# schematic.net
KiCad netlist of a schematic drawn in EAGLE
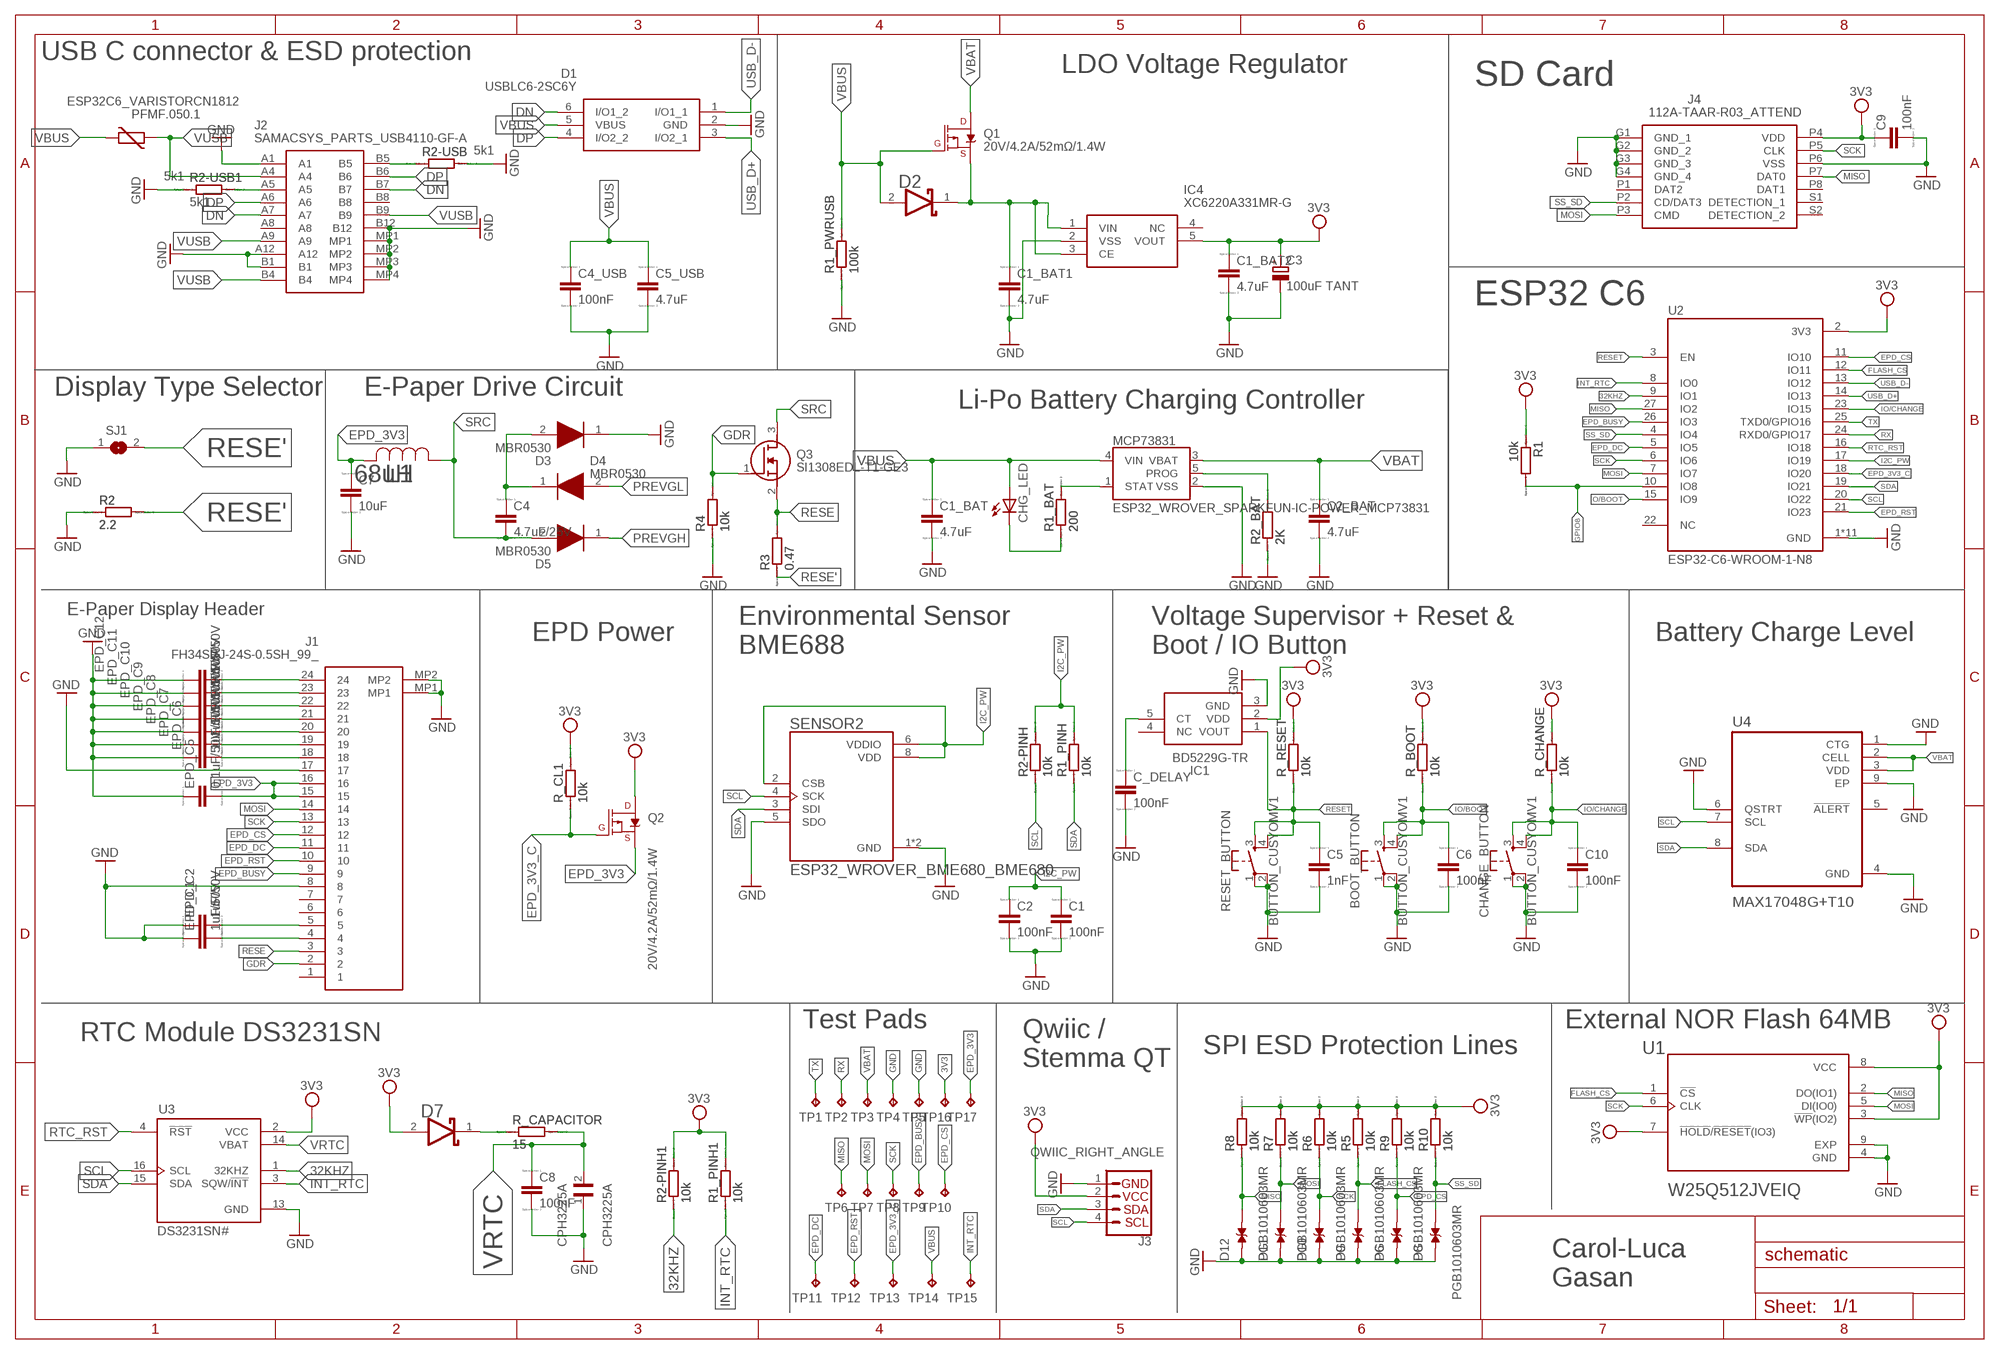
[diagram p0: schematic, sheet 1]

(export (version "E")
  (design (tool "Eeschema 10.0.6"))
  (components
    (comp (ref "BOOT_BUTTON")
      (value "BUTTON_CUSYOMV1")
      (footprint "eagle-import:MYBUTTON")
      (libsource (lib "eagle-import") (part "BUTTON_CUSYOMV1"))
    )
    (comp (ref "C1")
      (value "100nF")
      (footprint "eagle-import:ESP32_WROVER_EAGLE-LTSPICE_C0402")
      (libsource (lib "eagle-import") (part "ESP32_WROVER_EAGLE-LTSPICE_CC0402"))
    )
    (comp (ref "C1_BAT")
      (value "4.7uF")
      (footprint "eagle-import:ESP32_WROVER_EAGLE-LTSPICE_C0402")
      (libsource (lib "eagle-import") (part "ESP32_WROVER_EAGLE-LTSPICE_CC0402"))
    )
    (comp (ref "C1_BAT1")
      (value "4.7uF")
      (footprint "eagle-import:ESP32_WROVER_EAGLE-LTSPICE_C0402")
      (libsource (lib "eagle-import") (part "ESP32_WROVER_EAGLE-LTSPICE_CC0402"))
    )
    (comp (ref "C1_BAT2")
      (value "4.7uF")
      (footprint "eagle-import:ESP32_WROVER_EAGLE-LTSPICE_C0402")
      (libsource (lib "eagle-import") (part "ESP32_WROVER_EAGLE-LTSPICE_CC0402"))
    )
    (comp (ref "C2")
      (value "100nF")
      (footprint "eagle-import:ESP32_WROVER_EAGLE-LTSPICE_C0402")
      (libsource (lib "eagle-import") (part "ESP32_WROVER_EAGLE-LTSPICE_CC0402"))
    )
    (comp (ref "C2_BAT")
      (value "4.7uF")
      (footprint "eagle-import:ESP32_WROVER_EAGLE-LTSPICE_C0402")
      (libsource (lib "eagle-import") (part "ESP32_WROVER_EAGLE-LTSPICE_CC0402"))
    )
    (comp (ref "C3")
      (value "100uF TANT")
      (footprint "eagle-import:RCL_CT3528")
      (libsource (lib "eagle-import") (part "RCL_CPOL-EUCT3528"))
    )
    (comp (ref "C4")
      (value "4.7uF/25V")
      (footprint "eagle-import:ESP32_WROVER_EAGLE-LTSPICE_C0402")
      (libsource (lib "eagle-import") (part "ESP32_WROVER_EAGLE-LTSPICE_CC0402"))
    )
    (comp (ref "C4_USB")
      (value "100nF")
      (footprint "eagle-import:ESP32_WROVER_EAGLE-LTSPICE_C0402")
      (libsource (lib "eagle-import") (part "ESP32_WROVER_EAGLE-LTSPICE_CC0402"))
    )
    (comp (ref "C5")
      (value "1nF")
      (footprint "eagle-import:ESP32_WROVER_EAGLE-LTSPICE_C0402")
      (libsource (lib "eagle-import") (part "ESP32_WROVER_EAGLE-LTSPICE_CC0402"))
    )
    (comp (ref "C5_USB")
      (value "4.7uF")
      (footprint "eagle-import:ESP32_WROVER_EAGLE-LTSPICE_C0402")
      (libsource (lib "eagle-import") (part "ESP32_WROVER_EAGLE-LTSPICE_CC0402"))
    )
    (comp (ref "C6")
      (value "100nF")
      (footprint "eagle-import:ESP32_WROVER_EAGLE-LTSPICE_C0402")
      (libsource (lib "eagle-import") (part "ESP32_WROVER_EAGLE-LTSPICE_CC0402"))
    )
    (comp (ref "C7")
      (value "10uF")
      (footprint "eagle-import:ESP32_WROVER_EAGLE-LTSPICE_C0402")
      (libsource (lib "eagle-import") (part "ESP32_WROVER_EAGLE-LTSPICE_CC0402"))
    )
    (comp (ref "C8")
      (value "100nF")
      (footprint "eagle-import:ESP32_WROVER_EAGLE-LTSPICE_C0402")
      (libsource (lib "eagle-import") (part "ESP32_WROVER_EAGLE-LTSPICE_CC0402"))
    )
    (comp (ref "C9")
      (value "100nF")
      (footprint "eagle-import:ESP32_WROVER_EAGLE-LTSPICE_C0402")
      (libsource (lib "eagle-import") (part "ESP32_WROVER_EAGLE-LTSPICE_CC0402"))
    )
    (comp (ref "C10")
      (value "100nF")
      (footprint "eagle-import:ESP32_WROVER_EAGLE-LTSPICE_C0402")
      (libsource (lib "eagle-import") (part "ESP32_WROVER_EAGLE-LTSPICE_CC0402"))
    )
    (comp (ref "CHANGE_BUTTON")
      (value "BUTTON_CUSYOMV1")
      (footprint "eagle-import:MYBUTTON")
      (libsource (lib "eagle-import") (part "BUTTON_CUSYOMV1"))
    )
    (comp (ref "CHG_LED")
      (value "ADAFRUIT_LEDCHIP-LED0603")
      (footprint "eagle-import:ADAFRUIT_CHIP-LED0603")
      (libsource (lib "eagle-import") (part "ADAFRUIT_LEDCHIP-LED0603"))
    )
    (comp (ref "CPH3225A")
      (value "CPH3225A")
      (footprint "eagle-import:CAPCP3225X100N")
      (fields (field (name "MF") "Seiko Instruments"))
      (libsource (lib "eagle-import") (part "CPH3225A"))
    )
    (comp (ref "C_DELAY")
      (value "100nF")
      (footprint "eagle-import:ESP32_WROVER_EAGLE-LTSPICE_C0402")
      (libsource (lib "eagle-import") (part "ESP32_WROVER_EAGLE-LTSPICE_CC0402"))
    )
    (comp (ref "D1")
      (value "USBLC6-2SC6Y")
      (footprint "eagle-import:SOT95P280X145-6N")
      (fields (field (name "MF") "STMicroelectronics"))
      (libsource (lib "eagle-import") (part "USBLC6-2SC6Y"))
    )
    (comp (ref "D2")
      (value "ESP32_WROVER_AVX---SD0805S020S1R0_AVX_SD0805S020S1R0_0_0AVX_SD0805S020S1R0_0_0")
      (footprint "eagle-import:ESP32_WROVER_AVX---SD0805S020S1R0_AVX_SD0805S020S1R0_0")
      (fields
        (field (name "DIGIKEY_PART_NUMBER") "478-7800-1-ND")
        (field (name "MF") "AVX")
        (field (name "MOUSER_PART_NUMBER") "581-SD0805S020S1R0")
      )
      (libsource (lib "eagle-import") (part "ESP32_WROVER_AVX---SD0805S020S1R0_AVX_SD0805S020S1R0_0_0AVX_SD0805S020S1R0_0_0"))
    )
    (comp (ref "D3")
      (value "MBR0530")
      (footprint "eagle-import:SOD3716X135N")
      (fields (field (name "MF") "ON Semiconductor"))
      (libsource (lib "eagle-import") (part "MBR0530"))
    )
    (comp (ref "D4")
      (value "MBR0530")
      (footprint "eagle-import:SOD3716X135N")
      (fields (field (name "MF") "ON Semiconductor"))
      (libsource (lib "eagle-import") (part "MBR0530"))
    )
    (comp (ref "D5")
      (value "MBR0530")
      (footprint "eagle-import:SOD3716X135N")
      (fields (field (name "MF") "ON Semiconductor"))
      (libsource (lib "eagle-import") (part "MBR0530"))
    )
    (comp (ref "D6")
      (value "PGB1010603MR")
      (footprint "eagle-import:DIOC1608X36N")
      (fields (field (name "MF") "Littelfuse Inc."))
      (libsource (lib "eagle-import") (part "PGB1010603MR"))
    )
    (comp (ref "D7")
      (value "ESP32_WROVER_AVX---SD0805S020S1R0_AVX_SD0805S020S1R0_0_0AVX_SD0805S020S1R0_0_0")
      (footprint "eagle-import:ESP32_WROVER_AVX---SD0805S020S1R0_AVX_SD0805S020S1R0_0")
      (fields
        (field (name "DIGIKEY_PART_NUMBER") "478-7800-1-ND")
        (field (name "MF") "AVX")
        (field (name "MOUSER_PART_NUMBER") "581-SD0805S020S1R0")
      )
      (libsource (lib "eagle-import") (part "ESP32_WROVER_AVX---SD0805S020S1R0_AVX_SD0805S020S1R0_0_0AVX_SD0805S020S1R0_0_0"))
    )
    (comp (ref "D8")
      (value "PGB1010603MR")
      (footprint "eagle-import:DIOC1608X36N")
      (fields (field (name "MF") "Littelfuse Inc."))
      (libsource (lib "eagle-import") (part "PGB1010603MR"))
    )
    (comp (ref "D9")
      (value "PGB1010603MR")
      (footprint "eagle-import:DIOC1608X36N")
      (fields (field (name "MF") "Littelfuse Inc."))
      (libsource (lib "eagle-import") (part "PGB1010603MR"))
    )
    (comp (ref "D10")
      (value "PGB1010603MR")
      (footprint "eagle-import:DIOC1608X36N")
      (fields (field (name "MF") "Littelfuse Inc."))
      (libsource (lib "eagle-import") (part "PGB1010603MR"))
    )
    (comp (ref "D11")
      (value "PGB1010603MR")
      (footprint "eagle-import:DIOC1608X36N")
      (fields (field (name "MF") "Littelfuse Inc."))
      (libsource (lib "eagle-import") (part "PGB1010603MR"))
    )
    (comp (ref "D12")
      (value "PGB1010603MR")
      (footprint "eagle-import:DIOC1608X36N")
      (fields (field (name "MF") "Littelfuse Inc."))
      (libsource (lib "eagle-import") (part "PGB1010603MR"))
    )
    (comp (ref "EPD_C1")
      (value "1uF/50V")
      (footprint "eagle-import:ESP32_WROVER_EAGLE-LTSPICE_C0402")
      (libsource (lib "eagle-import") (part "ESP32_WROVER_EAGLE-LTSPICE_CC0402"))
    )
    (comp (ref "EPD_C2")
      (value "1uF/50V")
      (footprint "eagle-import:ESP32_WROVER_EAGLE-LTSPICE_C0402")
      (libsource (lib "eagle-import") (part "ESP32_WROVER_EAGLE-LTSPICE_CC0402"))
    )
    (comp (ref "EPD_C5")
      (value "0.1uF/50V")
      (footprint "eagle-import:ESP32_WROVER_EAGLE-LTSPICE_C0402")
      (libsource (lib "eagle-import") (part "ESP32_WROVER_EAGLE-LTSPICE_CC0402"))
    )
    (comp (ref "EPD_C6")
      (value "1uF/50V")
      (footprint "eagle-import:ESP32_WROVER_EAGLE-LTSPICE_C0402")
      (libsource (lib "eagle-import") (part "ESP32_WROVER_EAGLE-LTSPICE_CC0402"))
    )
    (comp (ref "EPD_C7")
      (value "1uF/50V")
      (footprint "eagle-import:ESP32_WROVER_EAGLE-LTSPICE_C0402")
      (libsource (lib "eagle-import") (part "ESP32_WROVER_EAGLE-LTSPICE_CC0402"))
    )
    (comp (ref "EPD_C8")
      (value "1uF/50V")
      (footprint "eagle-import:ESP32_WROVER_EAGLE-LTSPICE_C0402")
      (libsource (lib "eagle-import") (part "ESP32_WROVER_EAGLE-LTSPICE_CC0402"))
    )
    (comp (ref "EPD_C9")
      (value "1uF/50V")
      (footprint "eagle-import:ESP32_WROVER_EAGLE-LTSPICE_C0402")
      (libsource (lib "eagle-import") (part "ESP32_WROVER_EAGLE-LTSPICE_CC0402"))
    )
    (comp (ref "EPD_C10")
      (value "1uF/50V")
      (footprint "eagle-import:ESP32_WROVER_EAGLE-LTSPICE_C0402")
      (libsource (lib "eagle-import") (part "ESP32_WROVER_EAGLE-LTSPICE_CC0402"))
    )
    (comp (ref "EPD_C11")
      (value "1uF/50V")
      (footprint "eagle-import:ESP32_WROVER_EAGLE-LTSPICE_C0402")
      (libsource (lib "eagle-import") (part "ESP32_WROVER_EAGLE-LTSPICE_CC0402"))
    )
    (comp (ref "EPD_C12")
      (value "1uF/50V")
      (footprint "eagle-import:ESP32_WROVER_EAGLE-LTSPICE_C0402")
      (libsource (lib "eagle-import") (part "ESP32_WROVER_EAGLE-LTSPICE_CC0402"))
    )
    (comp (ref "IC1")
      (value "BD5229G-TR")
      (footprint "eagle-import:SOT95P280X125-5N")
      (fields (field (name "MOUSER_PART_NUMBER") "755-BD5229G-TR"))
      (libsource (lib "eagle-import") (part "BD5229G-TR"))
    )
    (comp (ref "IC4")
      (value "XC6220A331MR-G")
      (footprint "eagle-import:SOT95P280X120-5N")
      (fields (field (name "MOUSER_PART_NUMBER") "865-XC6220A331MR-G"))
      (libsource (lib "eagle-import") (part "XC6220A331MR-G"))
    )
    (comp (ref "J1")
      (value "FH34SRJ-24S-0.5SH_99_")
      (footprint "eagle-import:FH34SRJ24S05SH99")
      (fields
        (field (name "MANUFACTURER_PART_NUMBER") "FH34SRJ-24S-0.5SH(99)")
        (field (name "MOUSER_PART_NUMBER") "798-FH34SRJ24S05SH99")
      )
      (libsource (lib "eagle-import") (part "FH34SRJ-24S-0.5SH_99_"))
    )
    (comp (ref "J2")
      (value "SAMACSYS_PARTS_USB4110-GF-A")
      (footprint "eagle-import:SAMACSYS_PARTS_USB4110GFA")
      (fields
        (field (name "MANUFACTURER_PART_NUMBER") "USB4110-GF-A")
        (field (name "MOUSER_PART_NUMBER") "640-USB4110-GF-A")
      )
      (libsource (lib "eagle-import") (part "SAMACSYS_PARTS_USB4110-GF-A"))
    )
    (comp (ref "J3")
      (value "QWIIC_RIGHT_ANGLE")
      (footprint "eagle-import:JST04_1MM_RA")
      (libsource (lib "eagle-import") (part "QWIIC_CONNECTORJS-1MM"))
    )
    (comp (ref "J4")
      (value "112A-TAAR-R03_ATTEND")
      (footprint "eagle-import:112ATAARR03ATTEND")
      (fields (field (name "MANUFACTURER_PART_NUMBER") "112A-TAAR-R03 ATTEND"))
      (libsource (lib "eagle-import") (part "112A-TAAR-R03_ATTEND"))
    )
    (comp (ref "L1")
      (value "68uH")
      (footprint "eagle-import:IND_4828-WE-TPC_WRE")
      (fields
        (field (name "MANUFACTURER_PART_NUMBER") "744043680")
        (field (name "COPYRIGHT") "Copyright (C) 2024 Ultra Librarian. All rights reserved.")
      )
      (libsource (lib "eagle-import") (part "744043680IND_4828-WE-TPC_WRE"))
    )
    (comp (ref "MCP73831")
      (value "ESP32_WROVER_SPARKFUN-IC-POWER_MCP73831")
      (footprint "eagle-import:ESP32_WROVER_SPARKFUN-IC-POWER_SOT23-5")
      (libsource (lib "eagle-import") (part "ESP32_WROVER_SPARKFUN-IC-POWER_MCP73831"))
    )
    (comp (ref "PFMF.050.1")
      (value "ESP32C6_VARISTORCN1812")
      (footprint "eagle-import:ESP32C6_VARISTOR_CT_CN1812")
      (libsource (lib "eagle-import") (part "ESP32C6_VARISTORCN1812"))
    )
    (comp (ref "Q1")
      (value "20V/4.2A/52mΩ/1.4W")
      (footprint "eagle-import:ESP32_WROVER_SPARKFUN-DISCRETESEMI_SOT23-3")
      (libsource (lib "eagle-import") (part "ESP32_WROVER_SPARKFUN-DISCRETESEMI_MOSFET_PCH-DMG2305UX-7"))
    )
    (comp (ref "Q2")
      (value "20V/4.2A/52mΩ/1.4W")
      (footprint "eagle-import:ESP32_WROVER_SPARKFUN-DISCRETESEMI_SOT23-3")
      (libsource (lib "eagle-import") (part "ESP32_WROVER_SPARKFUN-DISCRETESEMI_MOSFET_PCH-DMG2305UX-7"))
    )
    (comp (ref "Q3")
      (value "SI1308EDL-T1-GE3")
      (footprint "eagle-import:SOT65P210X110-3N")
      (fields (field (name "MF") "Vishay Siliconix"))
      (libsource (lib "eagle-import") (part "SI1308EDL-T1-GE3"))
    )
    (comp (ref "R1")
      (value "10k")
      (footprint "eagle-import:ESP32_WROVER_EAGLE-LTSPICE_R0402")
      (libsource (lib "eagle-import") (part "ESP32_WROVER_EAGLE-LTSPICE_RR0402"))
    )
    (comp (ref "R1_BAT")
      (value "200")
      (footprint "eagle-import:ESP32_WROVER_EAGLE-LTSPICE_R0402")
      (libsource (lib "eagle-import") (part "ESP32_WROVER_EAGLE-LTSPICE_RR0402"))
    )
    (comp (ref "R1_PINH")
      (value "10k")
      (footprint "eagle-import:ESP32_WROVER_EAGLE-LTSPICE_R0402")
      (libsource (lib "eagle-import") (part "ESP32_WROVER_EAGLE-LTSPICE_RR0402"))
    )
    (comp (ref "R1_PINH1")
      (value "10k")
      (footprint "eagle-import:ESP32_WROVER_EAGLE-LTSPICE_R0402")
      (libsource (lib "eagle-import") (part "ESP32_WROVER_EAGLE-LTSPICE_RR0402"))
    )
    (comp (ref "R1_PWRUSB")
      (value "100k")
      (footprint "eagle-import:ESP32_WROVER_EAGLE-LTSPICE_R0402")
      (libsource (lib "eagle-import") (part "ESP32_WROVER_EAGLE-LTSPICE_RR0402"))
    )
    (comp (ref "R2")
      (value "2.2")
      (footprint "eagle-import:ESP32_WROVER_EAGLE-LTSPICE_R0402")
      (libsource (lib "eagle-import") (part "ESP32_WROVER_EAGLE-LTSPICE_RR0402"))
    )
    (comp (ref "R2-PINH")
      (value "10k")
      (footprint "eagle-import:ESP32_WROVER_EAGLE-LTSPICE_R0402")
      (libsource (lib "eagle-import") (part "ESP32_WROVER_EAGLE-LTSPICE_RR0402"))
    )
    (comp (ref "R2-PINH1")
      (value "10k")
      (footprint "eagle-import:ESP32_WROVER_EAGLE-LTSPICE_R0402")
      (libsource (lib "eagle-import") (part "ESP32_WROVER_EAGLE-LTSPICE_RR0402"))
    )
    (comp (ref "R2-USB")
      (value "5k1")
      (footprint "eagle-import:ESP32_WROVER_EAGLE-LTSPICE_R0402")
      (libsource (lib "eagle-import") (part "ESP32_WROVER_EAGLE-LTSPICE_RR0402"))
    )
    (comp (ref "R2-USB1")
      (value "5k1")
      (footprint "eagle-import:ESP32_WROVER_EAGLE-LTSPICE_R0402")
      (libsource (lib "eagle-import") (part "ESP32_WROVER_EAGLE-LTSPICE_RR0402"))
    )
    (comp (ref "R2_BAT")
      (value "2K")
      (footprint "eagle-import:ESP32_WROVER_EAGLE-LTSPICE_R0402")
      (libsource (lib "eagle-import") (part "ESP32_WROVER_EAGLE-LTSPICE_RR0402"))
    )
    (comp (ref "R3")
      (value "0.47")
      (footprint "eagle-import:ESP32_WROVER_EAGLE-LTSPICE_R0402")
      (libsource (lib "eagle-import") (part "ESP32_WROVER_EAGLE-LTSPICE_RR0402"))
    )
    (comp (ref "R4")
      (value "10k")
      (footprint "eagle-import:ESP32_WROVER_EAGLE-LTSPICE_R0402")
      (libsource (lib "eagle-import") (part "ESP32_WROVER_EAGLE-LTSPICE_RR0402"))
    )
    (comp (ref "R5")
      (value "10k")
      (footprint "eagle-import:ESP32_WROVER_EAGLE-LTSPICE_R0402")
      (libsource (lib "eagle-import") (part "ESP32_WROVER_EAGLE-LTSPICE_RR0402"))
    )
    (comp (ref "R6")
      (value "10k")
      (footprint "eagle-import:ESP32_WROVER_EAGLE-LTSPICE_R0402")
      (libsource (lib "eagle-import") (part "ESP32_WROVER_EAGLE-LTSPICE_RR0402"))
    )
    (comp (ref "R7")
      (value "10k")
      (footprint "eagle-import:ESP32_WROVER_EAGLE-LTSPICE_R0402")
      (libsource (lib "eagle-import") (part "ESP32_WROVER_EAGLE-LTSPICE_RR0402"))
    )
    (comp (ref "R8")
      (value "10k")
      (footprint "eagle-import:ESP32_WROVER_EAGLE-LTSPICE_R0402")
      (libsource (lib "eagle-import") (part "ESP32_WROVER_EAGLE-LTSPICE_RR0402"))
    )
    (comp (ref "R9")
      (value "10k")
      (footprint "eagle-import:ESP32_WROVER_EAGLE-LTSPICE_R0402")
      (libsource (lib "eagle-import") (part "ESP32_WROVER_EAGLE-LTSPICE_RR0402"))
    )
    (comp (ref "R10")
      (value "10k")
      (footprint "eagle-import:ESP32_WROVER_EAGLE-LTSPICE_R0402")
      (libsource (lib "eagle-import") (part "ESP32_WROVER_EAGLE-LTSPICE_RR0402"))
    )
    (comp (ref "RESET_BUTTON")
      (value "BUTTON_CUSYOMV1")
      (footprint "eagle-import:MYBUTTON")
      (libsource (lib "eagle-import") (part "BUTTON_CUSYOMV1"))
    )
    (comp (ref "R_BOOT")
      (value "10k")
      (footprint "eagle-import:ESP32_WROVER_EAGLE-LTSPICE_R0402")
      (libsource (lib "eagle-import") (part "ESP32_WROVER_EAGLE-LTSPICE_RR0402"))
    )
    (comp (ref "R_CAPACITOR")
      (value "15")
      (footprint "eagle-import:ESP32_WROVER_EAGLE-LTSPICE_R0402")
      (libsource (lib "eagle-import") (part "ESP32_WROVER_EAGLE-LTSPICE_RR0402"))
    )
    (comp (ref "R_CHANGE")
      (value "10k")
      (footprint "eagle-import:ESP32_WROVER_EAGLE-LTSPICE_R0402")
      (libsource (lib "eagle-import") (part "ESP32_WROVER_EAGLE-LTSPICE_RR0402"))
    )
    (comp (ref "R_CL1")
      (value "10k")
      (footprint "eagle-import:ESP32_WROVER_EAGLE-LTSPICE_R0402")
      (libsource (lib "eagle-import") (part "ESP32_WROVER_EAGLE-LTSPICE_RR0402"))
    )
    (comp (ref "R_RESET")
      (value "10k")
      (footprint "eagle-import:ESP32_WROVER_EAGLE-LTSPICE_R0402")
      (libsource (lib "eagle-import") (part "ESP32_WROVER_EAGLE-LTSPICE_RR0402"))
    )
    (comp (ref "SENSOR2")
      (value "ESP32_WROVER_BME680_BME680")
      (footprint "eagle-import:ESP32_WROVER_BME680_PSON80P300X300X100-8N")
      (fields (field (name "MF") "Bosch Sensortec") (field (name "MP") "BME680"))
      (libsource (lib "eagle-import") (part "ESP32_WROVER_BME680_BME680"))
    )
    (comp (ref "SJ1") (value "SJ") (footprint "eagle-import:SJ") (libsource (lib "eagle-import") (part "SJ")))
    (comp (ref "TP1")
      (value "TPTP20R")
      (footprint "eagle-import:TP20R")
      (libsource (lib "eagle-import") (part "TPTP20R"))
    )
    (comp (ref "TP2")
      (value "TPTP20R")
      (footprint "eagle-import:TP20R")
      (libsource (lib "eagle-import") (part "TPTP20R"))
    )
    (comp (ref "TP3")
      (value "TPTP20R")
      (footprint "eagle-import:TP20R")
      (libsource (lib "eagle-import") (part "TPTP20R"))
    )
    (comp (ref "TP4")
      (value "TPTP20R")
      (footprint "eagle-import:TP20R")
      (libsource (lib "eagle-import") (part "TPTP20R"))
    )
    (comp (ref "TP5")
      (value "TPTP20R")
      (footprint "eagle-import:TP20R")
      (libsource (lib "eagle-import") (part "TPTP20R"))
    )
    (comp (ref "TP6")
      (value "TPTP20R")
      (footprint "eagle-import:TP20R")
      (libsource (lib "eagle-import") (part "TPTP20R"))
    )
    (comp (ref "TP7")
      (value "TPTP20R")
      (footprint "eagle-import:TP20R")
      (libsource (lib "eagle-import") (part "TPTP20R"))
    )
    (comp (ref "TP8")
      (value "TPTP20R")
      (footprint "eagle-import:TP20R")
      (libsource (lib "eagle-import") (part "TPTP20R"))
    )
    (comp (ref "TP9")
      (value "TPTP20R")
      (footprint "eagle-import:TP20R")
      (libsource (lib "eagle-import") (part "TPTP20R"))
    )
    (comp (ref "TP10")
      (value "TPTP20R")
      (footprint "eagle-import:TP20R")
      (libsource (lib "eagle-import") (part "TPTP20R"))
    )
    (comp (ref "TP11")
      (value "TPTP20R")
      (footprint "eagle-import:TP20R")
      (libsource (lib "eagle-import") (part "TPTP20R"))
    )
    (comp (ref "TP12")
      (value "TPTP20R")
      (footprint "eagle-import:TP20R")
      (libsource (lib "eagle-import") (part "TPTP20R"))
    )
    (comp (ref "TP13")
      (value "TPTP20R")
      (footprint "eagle-import:TP20R")
      (libsource (lib "eagle-import") (part "TPTP20R"))
    )
    (comp (ref "TP14")
      (value "TPTP20R")
      (footprint "eagle-import:TP20R")
      (libsource (lib "eagle-import") (part "TPTP20R"))
    )
    (comp (ref "TP15")
      (value "TPTP20R")
      (footprint "eagle-import:TP20R")
      (libsource (lib "eagle-import") (part "TPTP20R"))
    )
    (comp (ref "TP16")
      (value "TPTP20R")
      (footprint "eagle-import:TP20R")
      (libsource (lib "eagle-import") (part "TPTP20R"))
    )
    (comp (ref "TP17")
      (value "TPTP20R")
      (footprint "eagle-import:TP20R")
      (libsource (lib "eagle-import") (part "TPTP20R"))
    )
    (comp (ref "U1")
      (value "W25Q512JVEIQ")
      (footprint "eagle-import:SON127P600X800X80-9N")
      (fields (field (name "MF") "Winbond Electronics"))
      (libsource (lib "eagle-import") (part "W25Q512JVEIQ"))
    )
    (comp (ref "U2")
      (value "ESP32-C6-WROOM-1-N8")
      (footprint "eagle-import:XCVR_ESP32-C6-WROOM-1-N8")
      (fields (field (name "MF") "Espressif Systems"))
      (libsource (lib "eagle-import") (part "ESP32-C6-WROOM-1-N8"))
    )
    (comp (ref "U3")
      (value "DS3231SN#")
      (footprint "eagle-import:SOIC127P1032X265-16N")
      (fields (field (name "MF") "Analog Devices"))
      (libsource (lib "eagle-import") (part "DS3231SN#"))
    )
    (comp (ref "U4")
      (value "MAX17048G+T10")
      (footprint "eagle-import:SON50P200X200X80-9N")
      (fields (field (name "MF") "Analog Devices"))
      (libsource (lib "eagle-import") (part "MAX17048G+T10"))
    )
  )
  (nets
    (net (code "1") (name "3V3") (class "Default")
      (node (ref "C1_BAT2") (pin "1") (pinfunction "1_1") (pintype "passive"))
      (node (ref "C3") (pin "+") (pinfunction "+_+") (pintype "passive"))
      (node (ref "C9") (pin "1") (pinfunction "1_1") (pintype "passive"))
      (node (ref "D7") (pin "2") (pinfunction "ANODE_2") (pintype "bidirectional"))
      (node (ref "IC1") (pin "2") (pinfunction "VDD_2") (pintype "bidirectional"))
      (node (ref "IC4") (pin "5") (pinfunction "VOUT_5") (pintype "bidirectional"))
      (node (ref "J3") (pin "2") (pinfunction "2_2") (pintype "power_in"))
      (node (ref "J4") (pin "P4") (pinfunction "VDD_P4") (pintype "bidirectional"))
      (node (ref "Q2") (pin "3") (pinfunction "D_3") (pintype "bidirectional"))
      (node (ref "R1") (pin "1") (pinfunction "1_1") (pintype "passive"))
      (node (ref "R10") (pin "2") (pinfunction "2_2") (pintype "passive"))
      (node (ref "R1_PINH1") (pin "2") (pinfunction "2_2") (pintype "passive"))
      (node (ref "R2-PINH1") (pin "2") (pinfunction "2_2") (pintype "passive"))
      (node (ref "R5") (pin "2") (pinfunction "2_2") (pintype "passive"))
      (node (ref "R6") (pin "2") (pinfunction "2_2") (pintype "passive"))
      (node (ref "R7") (pin "2") (pinfunction "2_2") (pintype "passive"))
      (node (ref "R8") (pin "2") (pinfunction "2_2") (pintype "passive"))
      (node (ref "R9") (pin "2") (pinfunction "2_2") (pintype "passive"))
      (node (ref "R_BOOT") (pin "2") (pinfunction "2_2") (pintype "passive"))
      (node (ref "R_CHANGE") (pin "2") (pinfunction "2_2") (pintype "passive"))
      (node (ref "R_CL1") (pin "2") (pinfunction "2_2") (pintype "passive"))
      (node (ref "R_RESET") (pin "2") (pinfunction "2_2") (pintype "passive"))
      (node (ref "TP16") (pin "TP") (pinfunction "TP_TP") (pintype "input"))
      (node (ref "U1") (pin "3") (pinfunction "~{WP}(IO2)_3") (pintype "bidirectional"))
      (node (ref "U1") (pin "7") (pinfunction "~{HOLD}/~{RESET}(IO3)_7") (pintype "bidirectional"))
      (node (ref "U1") (pin "8") (pinfunction "VCC_8") (pintype "power_in"))
      (node (ref "U2") (pin "2") (pinfunction "3V3_2") (pintype "power_in"))
      (node (ref "U3") (pin "2") (pinfunction "VCC_2") (pintype "power_in"))
    )
    (net (code "2") (name "32KHZ") (class "Default")
      (node (ref "R2-PINH1") (pin "1") (pinfunction "1_1") (pintype "passive"))
      (node (ref "U2") (pin "9") (pinfunction "IO1_9") (pintype "bidirectional"))
      (node (ref "U3") (pin "1") (pinfunction "32KHZ_1") (pintype "output"))
    )
    (net (code "3") (name "DN") (class "Default")
      (node (ref "D1") (pin "6") (pinfunction "I/O1_2_6") (pintype "bidirectional"))
      (node (ref "J2") (pin "A7") (pinfunction "A7_A7") (pintype "bidirectional"))
      (node (ref "J2") (pin "B7") (pinfunction "B7_B7") (pintype "bidirectional"))
    )
    (net (code "4") (name "DP") (class "Default")
      (node (ref "D1") (pin "4") (pinfunction "I/O2_2_4") (pintype "bidirectional"))
      (node (ref "J2") (pin "A6") (pinfunction "A6_A6") (pintype "bidirectional"))
      (node (ref "J2") (pin "B6") (pinfunction "B6_B6") (pintype "bidirectional"))
    )
    (net (code "5") (name "EPD_3V3") (class "Default")
      (node (ref "C7") (pin "1") (pinfunction "1_1") (pintype "passive"))
      (node (ref "EPD_C5") (pin "2") (pinfunction "2_2") (pintype "passive"))
      (node (ref "J1") (pin "15") (pinfunction "15_15") (pintype "bidirectional"))
      (node (ref "J1") (pin "16") (pinfunction "16_16") (pintype "bidirectional"))
      (node (ref "L1") (pin "2") (pinfunction "2_2") (pintype "passive"))
      (node (ref "Q2") (pin "2") (pinfunction "S_2") (pintype "bidirectional"))
      (node (ref "TP17") (pin "TP") (pinfunction "TP_TP") (pintype "input"))
    )
    (net (code "6") (name "EPD_3V3_C") (class "Default")
      (node (ref "Q2") (pin "1") (pinfunction "G_1") (pintype "bidirectional"))
      (node (ref "R_CL1") (pin "1") (pinfunction "1_1") (pintype "passive"))
      (node (ref "TP13") (pin "TP") (pinfunction "TP_TP") (pintype "input"))
      (node (ref "U2") (pin "18") (pinfunction "IO20_18") (pintype "bidirectional"))
    )
    (net (code "7") (name "EPD_BUSY") (class "Default")
      (node (ref "J1") (pin "9") (pinfunction "9_9") (pintype "bidirectional"))
      (node (ref "TP9") (pin "TP") (pinfunction "TP_TP") (pintype "input"))
      (node (ref "U2") (pin "26") (pinfunction "IO3_26") (pintype "bidirectional"))
    )
    (net (code "8") (name "EPD_CS") (class "Default")
      (node (ref "D6") (pin "2") (pinfunction "2_2") (pintype "passive"))
      (node (ref "J1") (pin "12") (pinfunction "12_12") (pintype "bidirectional"))
      (node (ref "R9") (pin "1") (pinfunction "1_1") (pintype "passive"))
      (node (ref "TP10") (pin "TP") (pinfunction "TP_TP") (pintype "input"))
      (node (ref "U2") (pin "11") (pinfunction "IO10_11") (pintype "bidirectional"))
    )
    (net (code "9") (name "EPD_DC") (class "Default")
      (node (ref "J1") (pin "11") (pinfunction "11_11") (pintype "bidirectional"))
      (node (ref "TP11") (pin "TP") (pinfunction "TP_TP") (pintype "input"))
      (node (ref "U2") (pin "5") (pinfunction "IO5_5") (pintype "bidirectional"))
    )
    (net (code "10") (name "EPD_RST") (class "Default")
      (node (ref "J1") (pin "10") (pinfunction "10_10") (pintype "bidirectional"))
      (node (ref "TP12") (pin "TP") (pinfunction "TP_TP") (pintype "input"))
      (node (ref "U2") (pin "21") (pinfunction "IO23_21") (pintype "bidirectional"))
    )
    (net (code "11") (name "FLASH_CS") (class "Default")
      (node (ref "D9") (pin "2") (pinfunction "2_2") (pintype "passive"))
      (node (ref "R5") (pin "1") (pinfunction "1_1") (pintype "passive"))
      (node (ref "U1") (pin "1") (pinfunction "~{CS}_1") (pintype "input"))
      (node (ref "U2") (pin "12") (pinfunction "IO11_12") (pintype "bidirectional"))
    )
    (net (code "12") (name "GDR") (class "Default")
      (node (ref "J1") (pin "2") (pinfunction "2_2") (pintype "bidirectional"))
      (node (ref "Q3") (pin "1") (pinfunction "G_1") (pintype "bidirectional"))
      (node (ref "R4") (pin "2") (pinfunction "2_2") (pintype "passive"))
    )
    (net (code "13") (name "GND") (class "Default")
      (node (ref "BOOT_BUTTON") (pin "1") (pinfunction "1_1") (pintype "passive"))
      (node (ref "BOOT_BUTTON") (pin "2") (pinfunction "2_2") (pintype "passive"))
      (node (ref "C1") (pin "2") (pinfunction "2_2") (pintype "passive"))
      (node (ref "C10") (pin "2") (pinfunction "2_2") (pintype "passive"))
      (node (ref "C1_BAT") (pin "2") (pinfunction "2_2") (pintype "passive"))
      (node (ref "C1_BAT1") (pin "2") (pinfunction "2_2") (pintype "passive"))
      (node (ref "C1_BAT2") (pin "2") (pinfunction "2_2") (pintype "passive"))
      (node (ref "C2") (pin "2") (pinfunction "2_2") (pintype "passive"))
      (node (ref "C2_BAT") (pin "2") (pinfunction "2_2") (pintype "passive"))
      (node (ref "C3") (pin "-") (pinfunction "-_-") (pintype "passive"))
      (node (ref "C4_USB") (pin "2") (pinfunction "2_2") (pintype "passive"))
      (node (ref "C5") (pin "2") (pinfunction "2_2") (pintype "passive"))
      (node (ref "C5_USB") (pin "2") (pinfunction "2_2") (pintype "passive"))
      (node (ref "C6") (pin "2") (pinfunction "2_2") (pintype "passive"))
      (node (ref "C7") (pin "2") (pinfunction "2_2") (pintype "passive"))
      (node (ref "C8") (pin "2") (pinfunction "2_2") (pintype "passive"))
      (node (ref "C9") (pin "2") (pinfunction "2_2") (pintype "passive"))
      (node (ref "CHANGE_BUTTON") (pin "1") (pinfunction "1_1") (pintype "passive"))
      (node (ref "CHANGE_BUTTON") (pin "2") (pinfunction "2_2") (pintype "passive"))
      (node (ref "CPH3225A") (pin "1") (pinfunction "1_1") (pintype "passive"))
      (node (ref "C_DELAY") (pin "2") (pinfunction "2_2") (pintype "passive"))
      (node (ref "D1") (pin "2") (pinfunction "GND_2") (pintype "bidirectional"))
      (node (ref "D10") (pin "1") (pinfunction "1_1") (pintype "passive"))
      (node (ref "D11") (pin "1") (pinfunction "1_1") (pintype "passive"))
      (node (ref "D12") (pin "1") (pinfunction "1_1") (pintype "passive"))
      (node (ref "D3") (pin "1") (pinfunction "K_1") (pintype "bidirectional"))
      (node (ref "D6") (pin "1") (pinfunction "1_1") (pintype "passive"))
      (node (ref "D8") (pin "1") (pinfunction "1_1") (pintype "passive"))
      (node (ref "D9") (pin "1") (pinfunction "1_1") (pintype "passive"))
      (node (ref "EPD_C1") (pin "1") (pinfunction "1_1") (pintype "passive"))
      (node (ref "EPD_C10") (pin "1") (pinfunction "1_1") (pintype "passive"))
      (node (ref "EPD_C11") (pin "1") (pinfunction "1_1") (pintype "passive"))
      (node (ref "EPD_C12") (pin "1") (pinfunction "1_1") (pintype "passive"))
      (node (ref "EPD_C2") (pin "1") (pinfunction "1_1") (pintype "passive"))
      (node (ref "EPD_C5") (pin "1") (pinfunction "1_1") (pintype "passive"))
      (node (ref "EPD_C6") (pin "1") (pinfunction "1_1") (pintype "passive"))
      (node (ref "EPD_C7") (pin "1") (pinfunction "1_1") (pintype "passive"))
      (node (ref "EPD_C8") (pin "1") (pinfunction "1_1") (pintype "passive"))
      (node (ref "EPD_C9") (pin "1") (pinfunction "1_1") (pintype "passive"))
      (node (ref "IC1") (pin "3") (pinfunction "GND_3") (pintype "bidirectional"))
      (node (ref "IC4") (pin "2") (pinfunction "VSS_2") (pintype "bidirectional"))
      (node (ref "J1") (pin "17") (pinfunction "17_17") (pintype "bidirectional"))
      (node (ref "J1") (pin "8") (pinfunction "8_8") (pintype "bidirectional"))
      (node (ref "J1") (pin "MP1") (pinfunction "MP1_MP1") (pintype "bidirectional"))
      (node (ref "J1") (pin "MP2") (pinfunction "MP2_MP2") (pintype "bidirectional"))
      (node (ref "J2") (pin "A1") (pinfunction "A1_A1") (pintype "bidirectional"))
      (node (ref "J2") (pin "A12") (pinfunction "A12_A12") (pintype "bidirectional"))
      (node (ref "J2") (pin "B1") (pinfunction "B1_B1") (pintype "bidirectional"))
      (node (ref "J2") (pin "B12") (pinfunction "B12_B12") (pintype "bidirectional"))
      (node (ref "J2") (pin "MP1") (pinfunction "MP1_MP1") (pintype "bidirectional"))
      (node (ref "J2") (pin "MP2") (pinfunction "MP2_MP2") (pintype "bidirectional"))
      (node (ref "J2") (pin "MP3") (pinfunction "MP3_MP3") (pintype "bidirectional"))
      (node (ref "J2") (pin "MP4") (pinfunction "MP4_MP4") (pintype "bidirectional"))
      (node (ref "J3") (pin "1") (pinfunction "1_1") (pintype "power_in"))
      (node (ref "J4") (pin "G1") (pinfunction "GND_1_G1") (pintype "bidirectional"))
      (node (ref "J4") (pin "G2") (pinfunction "GND_2_G2") (pintype "bidirectional"))
      (node (ref "J4") (pin "G3") (pinfunction "GND_3_G3") (pintype "bidirectional"))
      (node (ref "J4") (pin "G4") (pinfunction "GND_4_G4") (pintype "bidirectional"))
      (node (ref "J4") (pin "P6") (pinfunction "VSS_P6") (pintype "bidirectional"))
      (node (ref "MCP73831") (pin "2") (pinfunction "VSS_2") (pintype "power_in"))
      (node (ref "R1_PWRUSB") (pin "1") (pinfunction "1_1") (pintype "passive"))
      (node (ref "R2") (pin "1") (pinfunction "1_1") (pintype "passive"))
      (node (ref "R2-USB") (pin "2") (pinfunction "2_2") (pintype "passive"))
      (node (ref "R2-USB1") (pin "1") (pinfunction "1_1") (pintype "passive"))
      (node (ref "R2_BAT") (pin "1") (pinfunction "1_1") (pintype "passive"))
      (node (ref "R4") (pin "1") (pinfunction "1_1") (pintype "passive"))
      (node (ref "RESET_BUTTON") (pin "1") (pinfunction "1_1") (pintype "passive"))
      (node (ref "RESET_BUTTON") (pin "2") (pinfunction "2_2") (pintype "passive"))
      (node (ref "SENSOR2") (pin "1") (pinfunction "GND_1") (pintype "power_in"))
      (node (ref "SENSOR2") (pin "5") (pinfunction "SDO_5") (pintype "bidirectional"))
      (node (ref "SENSOR2") (pin "7") (pinfunction "GND_7") (pintype "power_in"))
      (node (ref "SJ1") (pin "1") (pinfunction "1_1") (pintype "passive"))
      (node (ref "TP4") (pin "TP") (pinfunction "TP_TP") (pintype "input"))
      (node (ref "TP5") (pin "TP") (pinfunction "TP_TP") (pintype "input"))
      (node (ref "U1") (pin "4") (pinfunction "GND_4") (pintype "power_in"))
      (node (ref "U1") (pin "9") (pinfunction "EXP_9") (pintype "passive"))
      (node (ref "U2") (pin "1") (pinfunction "GND_1") (pintype "power_in"))
      (node (ref "U2") (pin "28") (pinfunction "GND_28") (pintype "power_in"))
      (node (ref "U2") (pin "29_1") (pinfunction "GND_29_1") (pintype "power_in"))
      (node (ref "U2") (pin "29_2") (pinfunction "GND_29_2") (pintype "power_in"))
      (node (ref "U2") (pin "29_3") (pinfunction "GND_29_3") (pintype "power_in"))
      (node (ref "U2") (pin "29_4") (pinfunction "GND_29_4") (pintype "power_in"))
      (node (ref "U2") (pin "29_5") (pinfunction "GND_29_5") (pintype "power_in"))
      (node (ref "U2") (pin "29_6") (pinfunction "GND_29_6") (pintype "power_in"))
      (node (ref "U2") (pin "29_7") (pinfunction "GND_29_7") (pintype "power_in"))
      (node (ref "U2") (pin "29_8") (pinfunction "GND_29_8") (pintype "power_in"))
      (node (ref "U2") (pin "29_9") (pinfunction "GND_29_9") (pintype "power_in"))
      (node (ref "U3") (pin "13") (pinfunction "GND_13") (pintype "power_in"))
      (node (ref "U4") (pin "1") (pinfunction "CTG_1") (pintype "power_in"))
      (node (ref "U4") (pin "4") (pinfunction "GND_4") (pintype "power_in"))
      (node (ref "U4") (pin "6") (pinfunction "QSTRT_6") (pintype "input"))
      (node (ref "U4") (pin "9") (pinfunction "EP_9") (pintype "power_in"))
    )
    (net (code "14") (name "GPIO8") (class "Default")
      (node (ref "R1") (pin "2") (pinfunction "2_2") (pintype "passive"))
      (node (ref "U2") (pin "10") (pinfunction "IO8_10") (pintype "bidirectional"))
    )
    (net (code "15") (name "I2C_PW") (class "Default")
      (node (ref "C1") (pin "1") (pinfunction "1_1") (pintype "passive"))
      (node (ref "C2") (pin "1") (pinfunction "1_1") (pintype "passive"))
      (node (ref "R1_PINH") (pin "2") (pinfunction "2_2") (pintype "passive"))
      (node (ref "R2-PINH") (pin "2") (pinfunction "2_2") (pintype "passive"))
      (node (ref "SENSOR2") (pin "2") (pinfunction "CSB_2") (pintype "input"))
      (node (ref "SENSOR2") (pin "6") (pinfunction "VDDIO_6") (pintype "power_in"))
      (node (ref "SENSOR2") (pin "8") (pinfunction "VDD_8") (pintype "power_in"))
      (node (ref "U2") (pin "17") (pinfunction "IO19_17") (pintype "bidirectional"))
    )
    (net (code "16") (name "INT_RTC") (class "Default")
      (node (ref "R1_PINH1") (pin "1") (pinfunction "1_1") (pintype "passive"))
      (node (ref "TP15") (pin "TP") (pinfunction "TP_TP") (pintype "input"))
      (node (ref "U2") (pin "8") (pinfunction "IO0_8") (pintype "bidirectional"))
      (node (ref "U3") (pin "3") (pinfunction "SQW/~{INT}_3") (pintype "output"))
    )
    (net (code "17") (name "IO{slash}BOOT") (class "Default")
      (node (ref "BOOT_BUTTON") (pin "3") (pinfunction "3_3") (pintype "passive"))
      (node (ref "BOOT_BUTTON") (pin "4") (pinfunction "4_4") (pintype "passive"))
      (node (ref "C6") (pin "1") (pinfunction "1_1") (pintype "passive"))
      (node (ref "R_BOOT") (pin "1") (pinfunction "1_1") (pintype "passive"))
      (node (ref "U2") (pin "15") (pinfunction "IO9_15") (pintype "bidirectional"))
    )
    (net (code "18") (name "IO{slash}CHANGE") (class "Default")
      (node (ref "C10") (pin "1") (pinfunction "1_1") (pintype "passive"))
      (node (ref "CHANGE_BUTTON") (pin "3") (pinfunction "3_3") (pintype "passive"))
      (node (ref "CHANGE_BUTTON") (pin "4") (pinfunction "4_4") (pintype "passive"))
      (node (ref "R_CHANGE") (pin "1") (pinfunction "1_1") (pintype "passive"))
      (node (ref "U2") (pin "23") (pinfunction "IO15_23") (pintype "bidirectional"))
    )
    (net (code "19") (name "MISO") (class "Default")
      (node (ref "D12") (pin "2") (pinfunction "2_2") (pintype "passive"))
      (node (ref "J4") (pin "P7") (pinfunction "DAT0_P7") (pintype "bidirectional"))
      (node (ref "R8") (pin "1") (pinfunction "1_1") (pintype "passive"))
      (node (ref "TP6") (pin "TP") (pinfunction "TP_TP") (pintype "input"))
      (node (ref "U1") (pin "2") (pinfunction "DO(IO1)_2") (pintype "bidirectional"))
      (node (ref "U2") (pin "27") (pinfunction "IO2_27") (pintype "bidirectional"))
    )
    (net (code "20") (name "MOSI") (class "Default")
      (node (ref "D11") (pin "2") (pinfunction "2_2") (pintype "passive"))
      (node (ref "J1") (pin "14") (pinfunction "14_14") (pintype "bidirectional"))
      (node (ref "J4") (pin "P3") (pinfunction "CMD_P3") (pintype "bidirectional"))
      (node (ref "R7") (pin "1") (pinfunction "1_1") (pintype "passive"))
      (node (ref "TP7") (pin "TP") (pinfunction "TP_TP") (pintype "input"))
      (node (ref "U1") (pin "5") (pinfunction "DI(IO0)_5") (pintype "bidirectional"))
      (node (ref "U2") (pin "7") (pinfunction "IO7_7") (pintype "bidirectional"))
    )
    (net (code "21") (name "Net-(CHG_LED-PadC)") (class "Default")
      (node (ref "CHG_LED") (pin "C") (pinfunction "C_C") (pintype "passive"))
      (node (ref "R1_BAT") (pin "1") (pinfunction "1_1") (pintype "passive"))
    )
    (net (code "22") (name "Net-(D2-CATHODE)") (class "Default")
      (node (ref "C1_BAT1") (pin "1") (pinfunction "1_1") (pintype "passive"))
      (node (ref "D2") (pin "1") (pinfunction "CATHODE_1") (pintype "bidirectional"))
      (node (ref "IC4") (pin "1") (pinfunction "VIN_1") (pintype "bidirectional"))
      (node (ref "IC4") (pin "3") (pinfunction "CE_3") (pintype "bidirectional"))
      (node (ref "Q1") (pin "2") (pinfunction "S_2") (pintype "bidirectional"))
    )
    (net (code "23") (name "Net-(D3-A)") (class "Default")
      (node (ref "C4") (pin "1") (pinfunction "1_1") (pintype "passive"))
      (node (ref "D3") (pin "2") (pinfunction "A_2") (pintype "bidirectional"))
      (node (ref "D4") (pin "1") (pinfunction "K_1") (pintype "bidirectional"))
    )
    (net (code "24") (name "Net-(D7-CATHODE)") (class "Default")
      (node (ref "D7") (pin "1") (pinfunction "CATHODE_1") (pintype "bidirectional"))
      (node (ref "R_CAPACITOR") (pin "1") (pinfunction "1_1") (pintype "passive"))
    )
    (net (code "25") (name "Net-(EPD_C1-Pad2)") (class "Default")
      (node (ref "EPD_C1") (pin "2") (pinfunction "2_2") (pintype "passive"))
      (node (ref "J1") (pin "4") (pinfunction "4_4") (pintype "bidirectional"))
    )
    (net (code "26") (name "Net-(EPD_C2-Pad2)") (class "Default")
      (node (ref "EPD_C2") (pin "2") (pinfunction "2_2") (pintype "passive"))
      (node (ref "J1") (pin "5") (pinfunction "5_5") (pintype "bidirectional"))
    )
    (net (code "27") (name "Net-(EPD_C6-Pad2)") (class "Default")
      (node (ref "EPD_C6") (pin "2") (pinfunction "2_2") (pintype "passive"))
      (node (ref "J1") (pin "18") (pinfunction "18_18") (pintype "bidirectional"))
    )
    (net (code "28") (name "Net-(EPD_C7-Pad2)") (class "Default")
      (node (ref "EPD_C7") (pin "2") (pinfunction "2_2") (pintype "passive"))
      (node (ref "J1") (pin "19") (pinfunction "19_19") (pintype "bidirectional"))
    )
    (net (code "29") (name "Net-(EPD_C8-Pad2)") (class "Default")
      (node (ref "EPD_C8") (pin "2") (pinfunction "2_2") (pintype "passive"))
      (node (ref "J1") (pin "20") (pinfunction "20_20") (pintype "bidirectional"))
    )
    (net (code "30") (name "Net-(EPD_C9-Pad2)") (class "Default")
      (node (ref "EPD_C9") (pin "2") (pinfunction "2_2") (pintype "passive"))
      (node (ref "J1") (pin "21") (pinfunction "21_21") (pintype "bidirectional"))
    )
    (net (code "31") (name "Net-(EPD_C10-Pad2)") (class "Default")
      (node (ref "EPD_C10") (pin "2") (pinfunction "2_2") (pintype "passive"))
      (node (ref "J1") (pin "22") (pinfunction "22_22") (pintype "bidirectional"))
    )
    (net (code "32") (name "Net-(EPD_C11-Pad2)") (class "Default")
      (node (ref "EPD_C11") (pin "2") (pinfunction "2_2") (pintype "passive"))
      (node (ref "J1") (pin "23") (pinfunction "23_23") (pintype "bidirectional"))
    )
    (net (code "33") (name "Net-(EPD_C12-Pad2)") (class "Default")
      (node (ref "EPD_C12") (pin "2") (pinfunction "2_2") (pintype "passive"))
      (node (ref "J1") (pin "24") (pinfunction "24_24") (pintype "bidirectional"))
    )
    (net (code "34") (name "Net-(IC1-CT)") (class "Default")
      (node (ref "C_DELAY") (pin "1") (pinfunction "1_1") (pintype "passive"))
      (node (ref "IC1") (pin "5") (pinfunction "CT_5") (pintype "bidirectional"))
    )
    (net (code "35") (name "Net-(J2-PadA5)") (class "Default")
      (node (ref "J2") (pin "A5") (pinfunction "A5_A5") (pintype "bidirectional"))
      (node (ref "R2-USB1") (pin "2") (pinfunction "2_2") (pintype "passive"))
    )
    (net (code "36") (name "Net-(J2-PadB5)") (class "Default")
      (node (ref "J2") (pin "B5") (pinfunction "B5_B5") (pintype "bidirectional"))
      (node (ref "R2-USB") (pin "1") (pinfunction "1_1") (pintype "passive"))
    )
    (net (code "37") (name "Net-(MCP73831-PROG)") (class "Default")
      (node (ref "MCP73831") (pin "5") (pinfunction "PROG_5") (pintype "input"))
      (node (ref "R2_BAT") (pin "2") (pinfunction "2_2") (pintype "passive"))
    )
    (net (code "38") (name "Net-(MCP73831-STAT)") (class "Default")
      (node (ref "MCP73831") (pin "1") (pinfunction "STAT_1") (pintype "output"))
      (node (ref "R1_BAT") (pin "2") (pinfunction "2_2") (pintype "passive"))
    )
    (net (code "39") (name "PREVGH") (class "Default")
      (node (ref "D5") (pin "1") (pinfunction "K_1") (pintype "bidirectional"))
    )
    (net (code "40") (name "PREVGL") (class "Default")
      (node (ref "D4") (pin "2") (pinfunction "A_2") (pintype "bidirectional"))
    )
    (net (code "41") (name "RESE") (class "Default")
      (node (ref "J1") (pin "3") (pinfunction "3_3") (pintype "bidirectional"))
      (node (ref "Q3") (pin "2") (pinfunction "S_2") (pintype "bidirectional"))
      (node (ref "R3") (pin "2") (pinfunction "2_2") (pintype "passive"))
    )
    (net (code "42") (name "RESE'") (class "Default")
      (node (ref "R2") (pin "2") (pinfunction "2_2") (pintype "passive"))
      (node (ref "R3") (pin "1") (pinfunction "1_1") (pintype "passive"))
      (node (ref "SJ1") (pin "2") (pinfunction "2_2") (pintype "passive"))
    )
    (net (code "43") (name "RESET") (class "Default")
      (node (ref "C5") (pin "1") (pinfunction "1_1") (pintype "passive"))
      (node (ref "IC1") (pin "1") (pinfunction "VOUT_1") (pintype "bidirectional"))
      (node (ref "RESET_BUTTON") (pin "3") (pinfunction "3_3") (pintype "passive"))
      (node (ref "RESET_BUTTON") (pin "4") (pinfunction "4_4") (pintype "passive"))
      (node (ref "R_RESET") (pin "1") (pinfunction "1_1") (pintype "passive"))
      (node (ref "U2") (pin "3") (pinfunction "EN_3") (pintype "input"))
    )
    (net (code "44") (name "RTC_RST") (class "Default")
      (node (ref "U2") (pin "16") (pinfunction "IO18_16") (pintype "bidirectional"))
      (node (ref "U3") (pin "4") (pinfunction "~{RST}_4") (pintype "input"))
    )
    (net (code "45") (name "RX") (class "Default")
      (node (ref "TP2") (pin "TP") (pinfunction "TP_TP") (pintype "input"))
      (node (ref "U2") (pin "24") (pinfunction "RXD0/GPIO17_24") (pintype "bidirectional"))
    )
    (net (code "46") (name "SCK") (class "Default")
      (node (ref "D10") (pin "2") (pinfunction "2_2") (pintype "passive"))
      (node (ref "J1") (pin "13") (pinfunction "13_13") (pintype "bidirectional"))
      (node (ref "J4") (pin "P5") (pinfunction "CLK_P5") (pintype "bidirectional"))
      (node (ref "R6") (pin "1") (pinfunction "1_1") (pintype "passive"))
      (node (ref "TP8") (pin "TP") (pinfunction "TP_TP") (pintype "input"))
      (node (ref "U1") (pin "6") (pinfunction "CLK_6") (pintype "input"))
      (node (ref "U2") (pin "6") (pinfunction "IO6_6") (pintype "bidirectional"))
    )
    (net (code "47") (name "SCL") (class "Default")
      (node (ref "J3") (pin "4") (pinfunction "4_4") (pintype "passive"))
      (node (ref "R2-PINH") (pin "1") (pinfunction "1_1") (pintype "passive"))
      (node (ref "SENSOR2") (pin "4") (pinfunction "SCK_4") (pintype "input"))
      (node (ref "U2") (pin "20") (pinfunction "IO22_20") (pintype "bidirectional"))
      (node (ref "U3") (pin "16") (pinfunction "SCL_16") (pintype "input"))
      (node (ref "U4") (pin "7") (pinfunction "SCL_7") (pintype "input"))
    )
    (net (code "48") (name "SDA") (class "Default")
      (node (ref "J3") (pin "3") (pinfunction "3_3") (pintype "passive"))
      (node (ref "R1_PINH") (pin "1") (pinfunction "1_1") (pintype "passive"))
      (node (ref "SENSOR2") (pin "3") (pinfunction "SDI_3") (pintype "bidirectional"))
      (node (ref "U2") (pin "19") (pinfunction "IO21_19") (pintype "bidirectional"))
      (node (ref "U3") (pin "15") (pinfunction "SDA_15") (pintype "bidirectional"))
      (node (ref "U4") (pin "8") (pinfunction "SDA_8") (pintype "bidirectional"))
    )
    (net (code "49") (name "SRC") (class "Default")
      (node (ref "C4") (pin "2") (pinfunction "2_2") (pintype "passive"))
      (node (ref "D5") (pin "2") (pinfunction "A_2") (pintype "bidirectional"))
      (node (ref "L1") (pin "1") (pinfunction "1_1") (pintype "passive"))
      (node (ref "Q3") (pin "3") (pinfunction "D_3") (pintype "bidirectional"))
    )
    (net (code "50") (name "SS_SD") (class "Default")
      (node (ref "D8") (pin "2") (pinfunction "2_2") (pintype "passive"))
      (node (ref "J4") (pin "P2") (pinfunction "CD/DAT3_P2") (pintype "bidirectional"))
      (node (ref "R10") (pin "1") (pinfunction "1_1") (pintype "passive"))
      (node (ref "U2") (pin "4") (pinfunction "IO4_4") (pintype "bidirectional"))
    )
    (net (code "51") (name "TX") (class "Default")
      (node (ref "TP1") (pin "TP") (pinfunction "TP_TP") (pintype "input"))
      (node (ref "U2") (pin "25") (pinfunction "TXD0/GPIO16_25") (pintype "bidirectional"))
    )
    (net (code "52") (name "USB_D+") (class "Default")
      (node (ref "D1") (pin "3") (pinfunction "I/O2_1_3") (pintype "bidirectional"))
      (node (ref "U2") (pin "14") (pinfunction "IO13_14") (pintype "bidirectional"))
    )
    (net (code "53") (name "USB_D-") (class "Default")
      (node (ref "D1") (pin "1") (pinfunction "I/O1_1_1") (pintype "bidirectional"))
      (node (ref "U2") (pin "13") (pinfunction "IO12_13") (pintype "bidirectional"))
    )
    (net (code "54") (name "VBAT") (class "Default")
      (node (ref "C2_BAT") (pin "1") (pinfunction "1_1") (pintype "passive"))
      (node (ref "MCP73831") (pin "3") (pinfunction "VBAT_3") (pintype "power_in"))
      (node (ref "Q1") (pin "3") (pinfunction "D_3") (pintype "bidirectional"))
      (node (ref "TP3") (pin "TP") (pinfunction "TP_TP") (pintype "input"))
      (node (ref "U4") (pin "2") (pinfunction "CELL_2") (pintype "power_in"))
      (node (ref "U4") (pin "3") (pinfunction "VDD_3") (pintype "power_in"))
    )
    (net (code "55") (name "VBUS") (class "Default")
      (node (ref "C1_BAT") (pin "1") (pinfunction "1_1") (pintype "passive"))
      (node (ref "C4_USB") (pin "1") (pinfunction "1_1") (pintype "passive"))
      (node (ref "C5_USB") (pin "1") (pinfunction "1_1") (pintype "passive"))
      (node (ref "CHG_LED") (pin "A") (pinfunction "A_A") (pintype "passive"))
      (node (ref "D1") (pin "5") (pinfunction "VBUS_5") (pintype "bidirectional"))
      (node (ref "D2") (pin "2") (pinfunction "ANODE_2") (pintype "bidirectional"))
      (node (ref "MCP73831") (pin "4") (pinfunction "VIN_4") (pintype "power_in"))
      (node (ref "PFMF.050.1") (pin "2") (pinfunction "2_2") (pintype "passive"))
      (node (ref "Q1") (pin "1") (pinfunction "G_1") (pintype "bidirectional"))
      (node (ref "R1_PWRUSB") (pin "2") (pinfunction "2_2") (pintype "passive"))
      (node (ref "TP14") (pin "TP") (pinfunction "TP_TP") (pintype "input"))
    )
    (net (code "56") (name "VRTC") (class "Default")
      (node (ref "C8") (pin "1") (pinfunction "1_1") (pintype "passive"))
      (node (ref "CPH3225A") (pin "2") (pinfunction "2_2") (pintype "passive"))
      (node (ref "R_CAPACITOR") (pin "2") (pinfunction "2_2") (pintype "passive"))
      (node (ref "U3") (pin "14") (pinfunction "VBAT_14") (pintype "power_in"))
    )
    (net (code "57") (name "VUSB") (class "Default")
      (node (ref "J2") (pin "A4") (pinfunction "A4_A4") (pintype "bidirectional"))
      (node (ref "J2") (pin "A9") (pinfunction "A9_A9") (pintype "bidirectional"))
      (node (ref "J2") (pin "B4") (pinfunction "B4_B4") (pintype "bidirectional"))
      (node (ref "J2") (pin "B9") (pinfunction "B9_B9") (pintype "bidirectional"))
      (node (ref "PFMF.050.1") (pin "1") (pinfunction "1_1") (pintype "passive"))
    )
    (net (code "58") (name "unconnected-(IC1-NC-Pad4)") (class "Default")
      (node (ref "IC1") (pin "4") (pinfunction "NC_4") (pintype "no_connect"))
    )
    (net (code "59") (name "unconnected-(IC4-NC-Pad4)") (class "Default")
      (node (ref "IC4") (pin "4") (pinfunction "NC_4") (pintype "no_connect"))
    )
    (net (code "60") (name "unconnected-(J1-Pad1)") (class "Default")
      (node (ref "J1") (pin "1") (pinfunction "1_1") (pintype "bidirectional"))
    )
    (net (code "61") (name "unconnected-(J1-Pad6)") (class "Default")
      (node (ref "J1") (pin "6") (pinfunction "6_6") (pintype "bidirectional"))
    )
    (net (code "62") (name "unconnected-(J1-Pad7)") (class "Default")
      (node (ref "J1") (pin "7") (pinfunction "7_7") (pintype "bidirectional"))
    )
    (net (code "63") (name "unconnected-(J2-PadA8)") (class "Default")
      (node (ref "J2") (pin "A8") (pinfunction "A8_A8") (pintype "bidirectional"))
    )
    (net (code "64") (name "unconnected-(J2-PadB8)") (class "Default")
      (node (ref "J2") (pin "B8") (pinfunction "B8_B8") (pintype "bidirectional"))
    )
    (net (code "65") (name "unconnected-(J4-DAT1-PadP8)") (class "Default")
      (node (ref "J4") (pin "P8") (pinfunction "DAT1_P8") (pintype "bidirectional"))
    )
    (net (code "66") (name "unconnected-(J4-DAT2-PadP1)") (class "Default")
      (node (ref "J4") (pin "P1") (pinfunction "DAT2_P1") (pintype "bidirectional"))
    )
    (net (code "67") (name "unconnected-(J4-DETECTION_1-PadS1)") (class "Default")
      (node (ref "J4") (pin "S1") (pinfunction "DETECTION_1_S1") (pintype "bidirectional"))
    )
    (net (code "68") (name "unconnected-(J4-DETECTION_2-PadS2)") (class "Default")
      (node (ref "J4") (pin "S2") (pinfunction "DETECTION_2_S2") (pintype "bidirectional"))
    )
    (net (code "69") (name "unconnected-(U2-NC-Pad22)") (class "Default")
      (node (ref "U2") (pin "22") (pinfunction "NC_22") (pintype "no_connect"))
    )
    (net (code "70") (name "unconnected-(U4-~{ALERT}-Pad5)") (class "Default")
      (node (ref "U4") (pin "5") (pinfunction "~{ALERT}_5") (pintype "output"))
    )
  )
)
